# data_right.net
KiCad netlist of a schematic drawn in Altium Designer
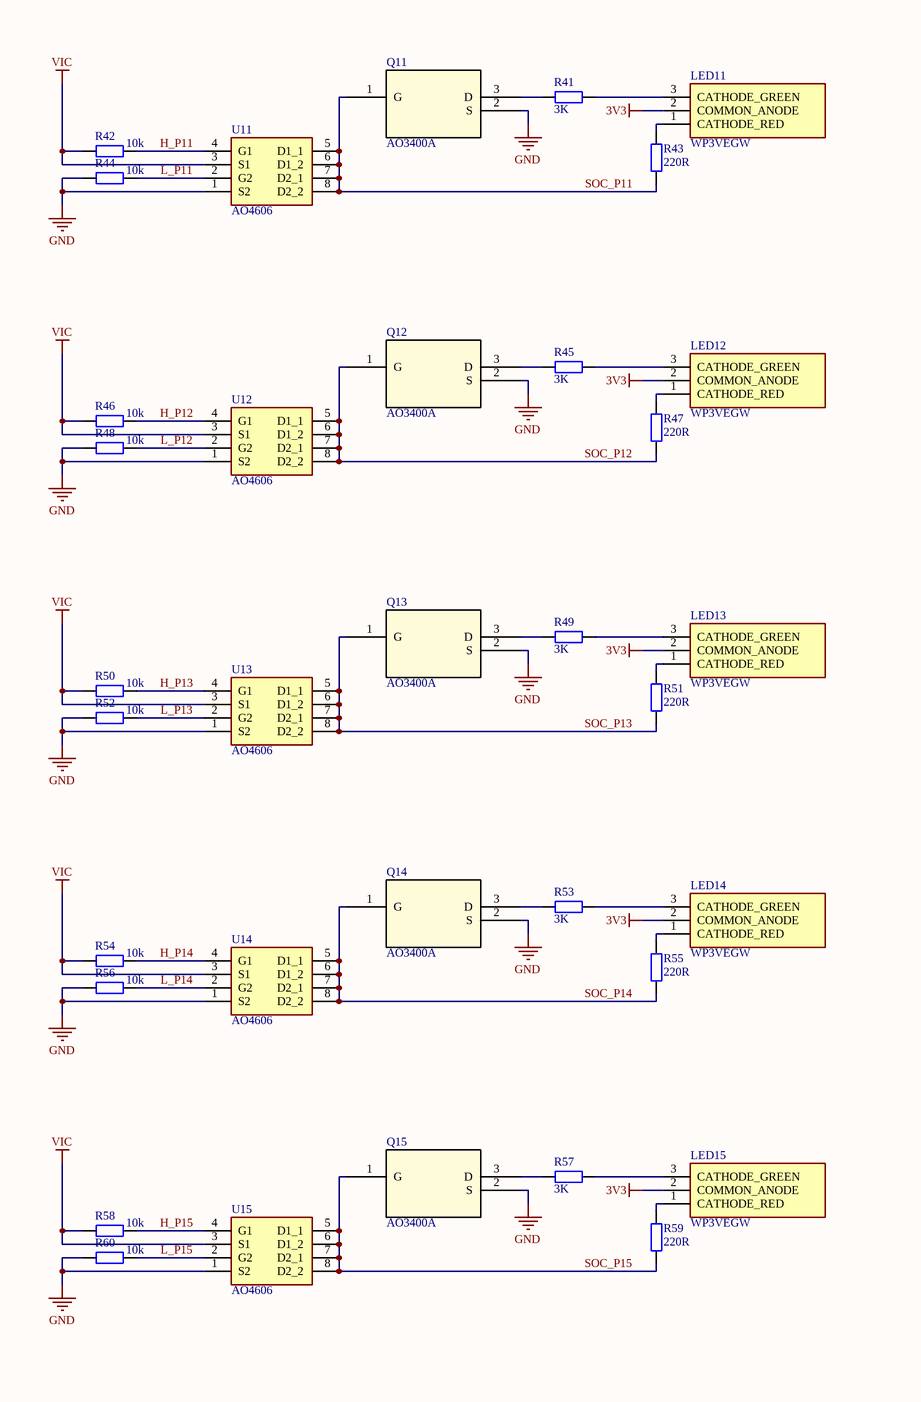
[diagram p0: data_right.SchDoc, top]
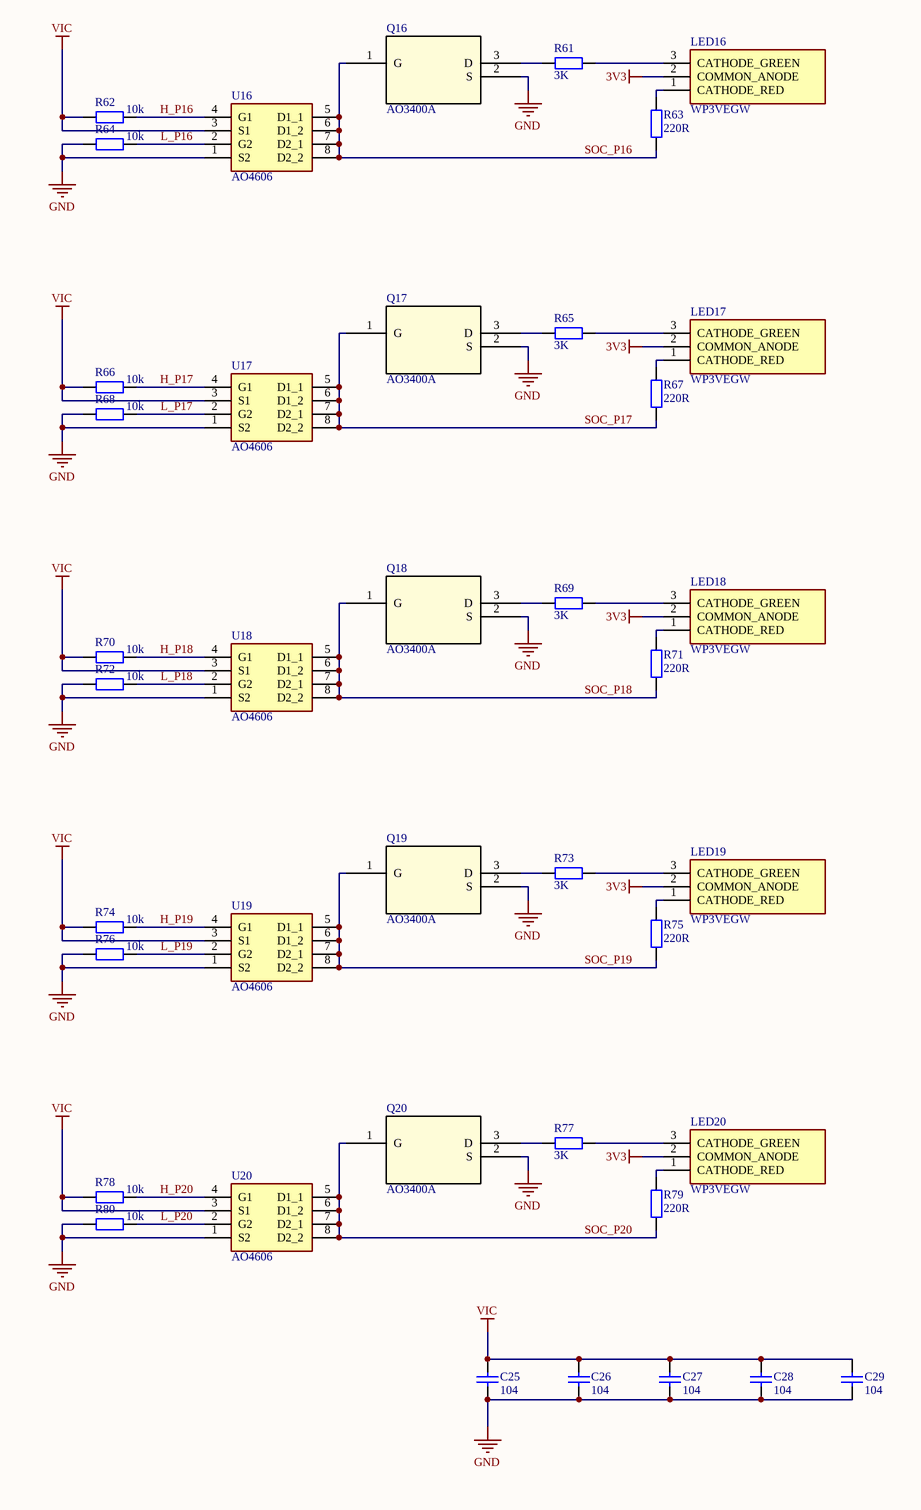
[diagram p1: data_right.SchDoc, bottom]

(export (version "E")
  (design (tool "Eeschema 10.0.6"))
  (components
    (comp (ref "C25")
      (value "104")
      (footprint "tu 0805")
      (description "Dán")
      (libsource (lib "thuvien") (part "Tu 0805 106 16V 10%"))
    )
    (comp (ref "C26")
      (value "104")
      (footprint "tu 0805")
      (description "Dán")
      (libsource (lib "thuvien") (part "Tu 0805 106 16V 10%"))
    )
    (comp (ref "C27")
      (value "104")
      (footprint "tu 0805")
      (description "Dán")
      (libsource (lib "thuvien") (part "Tu 0805 106 16V 10%"))
    )
    (comp (ref "C28")
      (value "104")
      (footprint "tu 0805")
      (description "Dán")
      (libsource (lib "thuvien") (part "Tu 0805 106 16V 10%"))
    )
    (comp (ref "C29")
      (value "104")
      (footprint "tu 0805")
      (description "Dán")
      (libsource (lib "thuvien") (part "Tu 0805 106 16V 10%"))
    )
    (comp (ref "LED11")
      (value "WP3VEGW")
      (footprint "WP3VEGW")
      (description "LED RED/GREEN 3mm")
      (fields (field (name "MOUSER PART NUMBER") "604-WP3VEGW"))
      (libsource (lib "thuvien") (part "WP3VEGW"))
    )
    (comp (ref "LED12")
      (value "WP3VEGW")
      (footprint "WP3VEGW")
      (description "LED RED/GREEN 3mm")
      (fields (field (name "MOUSER PART NUMBER") "604-WP3VEGW"))
      (libsource (lib "thuvien") (part "WP3VEGW"))
    )
    (comp (ref "LED13")
      (value "WP3VEGW")
      (footprint "WP3VEGW")
      (description "LED RED/GREEN 3mm")
      (fields (field (name "MOUSER PART NUMBER") "604-WP3VEGW"))
      (libsource (lib "thuvien") (part "WP3VEGW"))
    )
    (comp (ref "LED14")
      (value "WP3VEGW")
      (footprint "WP3VEGW")
      (description "LED RED/GREEN 3mm")
      (fields (field (name "MOUSER PART NUMBER") "604-WP3VEGW"))
      (libsource (lib "thuvien") (part "WP3VEGW"))
    )
    (comp (ref "LED15")
      (value "WP3VEGW")
      (footprint "WP3VEGW")
      (description "LED RED/GREEN 3mm")
      (fields (field (name "MOUSER PART NUMBER") "604-WP3VEGW"))
      (libsource (lib "thuvien") (part "WP3VEGW"))
    )
    (comp (ref "LED16")
      (value "WP3VEGW")
      (footprint "WP3VEGW")
      (description "LED RED/GREEN 3mm")
      (fields (field (name "MOUSER PART NUMBER") "604-WP3VEGW"))
      (libsource (lib "thuvien") (part "WP3VEGW"))
    )
    (comp (ref "LED17")
      (value "WP3VEGW")
      (footprint "WP3VEGW")
      (description "LED RED/GREEN 3mm")
      (fields (field (name "MOUSER PART NUMBER") "604-WP3VEGW"))
      (libsource (lib "thuvien") (part "WP3VEGW"))
    )
    (comp (ref "LED18")
      (value "WP3VEGW")
      (footprint "WP3VEGW")
      (description "LED RED/GREEN 3mm")
      (fields (field (name "MOUSER PART NUMBER") "604-WP3VEGW"))
      (libsource (lib "thuvien") (part "WP3VEGW"))
    )
    (comp (ref "LED19")
      (value "WP3VEGW")
      (footprint "WP3VEGW")
      (description "LED RED/GREEN 3mm")
      (fields (field (name "MOUSER PART NUMBER") "604-WP3VEGW"))
      (libsource (lib "thuvien") (part "WP3VEGW"))
    )
    (comp (ref "LED20")
      (value "WP3VEGW")
      (footprint "WP3VEGW")
      (description "LED RED/GREEN 3mm")
      (fields (field (name "MOUSER PART NUMBER") "604-WP3VEGW"))
      (libsource (lib "thuvien") (part "WP3VEGW"))
    )
    (comp (ref "Q11")
      (value "AO3400A")
      (footprint "SOT-23-3L_AOS")
      (description "N-MOSFET")
      (fields (field (name "COPYRIGHT") "Copyright (C) 2023 Ultra Librarian. All rights reserved."))
      (libsource (lib "thuvien") (part "AO3400A"))
    )
    (comp (ref "Q12")
      (value "AO3400A")
      (footprint "SOT-23-3L_AOS")
      (description "N-MOSFET")
      (fields (field (name "COPYRIGHT") "Copyright (C) 2023 Ultra Librarian. All rights reserved."))
      (libsource (lib "thuvien") (part "AO3400A"))
    )
    (comp (ref "Q13")
      (value "AO3400A")
      (footprint "SOT-23-3L_AOS")
      (description "N-MOSFET")
      (fields (field (name "COPYRIGHT") "Copyright (C) 2023 Ultra Librarian. All rights reserved."))
      (libsource (lib "thuvien") (part "AO3400A"))
    )
    (comp (ref "Q14")
      (value "AO3400A")
      (footprint "SOT-23-3L_AOS")
      (description "N-MOSFET")
      (fields (field (name "COPYRIGHT") "Copyright (C) 2023 Ultra Librarian. All rights reserved."))
      (libsource (lib "thuvien") (part "AO3400A"))
    )
    (comp (ref "Q15")
      (value "AO3400A")
      (footprint "SOT-23-3L_AOS")
      (description "N-MOSFET")
      (fields (field (name "COPYRIGHT") "Copyright (C) 2023 Ultra Librarian. All rights reserved."))
      (libsource (lib "thuvien") (part "AO3400A"))
    )
    (comp (ref "Q16")
      (value "AO3400A")
      (footprint "SOT-23-3L_AOS")
      (description "N-MOSFET")
      (fields (field (name "COPYRIGHT") "Copyright (C) 2023 Ultra Librarian. All rights reserved."))
      (libsource (lib "thuvien") (part "AO3400A"))
    )
    (comp (ref "Q17")
      (value "AO3400A")
      (footprint "SOT-23-3L_AOS")
      (description "N-MOSFET")
      (fields (field (name "COPYRIGHT") "Copyright (C) 2023 Ultra Librarian. All rights reserved."))
      (libsource (lib "thuvien") (part "AO3400A"))
    )
    (comp (ref "Q18")
      (value "AO3400A")
      (footprint "SOT-23-3L_AOS")
      (description "N-MOSFET")
      (fields (field (name "COPYRIGHT") "Copyright (C) 2023 Ultra Librarian. All rights reserved."))
      (libsource (lib "thuvien") (part "AO3400A"))
    )
    (comp (ref "Q19")
      (value "AO3400A")
      (footprint "SOT-23-3L_AOS")
      (description "N-MOSFET")
      (fields (field (name "COPYRIGHT") "Copyright (C) 2023 Ultra Librarian. All rights reserved."))
      (libsource (lib "thuvien") (part "AO3400A"))
    )
    (comp (ref "Q20")
      (value "AO3400A")
      (footprint "SOT-23-3L_AOS")
      (description "N-MOSFET")
      (fields (field (name "COPYRIGHT") "Copyright (C) 2023 Ultra Librarian. All rights reserved."))
      (libsource (lib "thuvien") (part "AO3400A"))
    )
    (comp (ref "R41")
      (value "3K")
      (footprint "tro smd 0805")
      (description "Dán")
      (libsource (lib "thuvien") (part "Tro 0805 1% 10k"))
    )
    (comp (ref "R42")
      (value "10k")
      (footprint "tro smd 0805")
      (description "Dán")
      (libsource (lib "thuvien") (part "Tro 0805 1% 10k"))
    )
    (comp (ref "R43")
      (value "220R")
      (footprint "tro smd 0805")
      (description "Dán")
      (libsource (lib "thuvien") (part "Tro 0805 1% 10k"))
    )
    (comp (ref "R44")
      (value "10k")
      (footprint "tro smd 0805")
      (description "Dán")
      (libsource (lib "thuvien") (part "Tro 0805 1% 10k"))
    )
    (comp (ref "R45")
      (value "3K")
      (footprint "tro smd 0805")
      (description "Dán")
      (libsource (lib "thuvien") (part "Tro 0805 1% 10k"))
    )
    (comp (ref "R46")
      (value "10k")
      (footprint "tro smd 0805")
      (description "Dán")
      (libsource (lib "thuvien") (part "Tro 0805 1% 10k"))
    )
    (comp (ref "R47")
      (value "220R")
      (footprint "tro smd 0805")
      (description "Dán")
      (libsource (lib "thuvien") (part "Tro 0805 1% 10k"))
    )
    (comp (ref "R48")
      (value "10k")
      (footprint "tro smd 0805")
      (description "Dán")
      (libsource (lib "thuvien") (part "Tro 0805 1% 10k"))
    )
    (comp (ref "R49")
      (value "3K")
      (footprint "tro smd 0805")
      (description "Dán")
      (libsource (lib "thuvien") (part "Tro 0805 1% 10k"))
    )
    (comp (ref "R50")
      (value "10k")
      (footprint "tro smd 0805")
      (description "Dán")
      (libsource (lib "thuvien") (part "Tro 0805 1% 10k"))
    )
    (comp (ref "R51")
      (value "220R")
      (footprint "tro smd 0805")
      (description "Dán")
      (libsource (lib "thuvien") (part "Tro 0805 1% 10k"))
    )
    (comp (ref "R52")
      (value "10k")
      (footprint "tro smd 0805")
      (description "Dán")
      (libsource (lib "thuvien") (part "Tro 0805 1% 10k"))
    )
    (comp (ref "R53")
      (value "3K")
      (footprint "tro smd 0805")
      (description "Dán")
      (libsource (lib "thuvien") (part "Tro 0805 1% 10k"))
    )
    (comp (ref "R54")
      (value "10k")
      (footprint "tro smd 0805")
      (description "Dán")
      (libsource (lib "thuvien") (part "Tro 0805 1% 10k"))
    )
    (comp (ref "R55")
      (value "220R")
      (footprint "tro smd 0805")
      (description "Dán")
      (libsource (lib "thuvien") (part "Tro 0805 1% 10k"))
    )
    (comp (ref "R56")
      (value "10k")
      (footprint "tro smd 0805")
      (description "Dán")
      (libsource (lib "thuvien") (part "Tro 0805 1% 10k"))
    )
    (comp (ref "R57")
      (value "3K")
      (footprint "tro smd 0805")
      (description "Dán")
      (libsource (lib "thuvien") (part "Tro 0805 1% 10k"))
    )
    (comp (ref "R58")
      (value "10k")
      (footprint "tro smd 0805")
      (description "Dán")
      (libsource (lib "thuvien") (part "Tro 0805 1% 10k"))
    )
    (comp (ref "R59")
      (value "220R")
      (footprint "tro smd 0805")
      (description "Dán")
      (libsource (lib "thuvien") (part "Tro 0805 1% 10k"))
    )
    (comp (ref "R60")
      (value "10k")
      (footprint "tro smd 0805")
      (description "Dán")
      (libsource (lib "thuvien") (part "Tro 0805 1% 10k"))
    )
    (comp (ref "R61")
      (value "3K")
      (footprint "tro smd 0805")
      (description "Dán")
      (libsource (lib "thuvien") (part "Tro 0805 1% 10k"))
    )
    (comp (ref "R62")
      (value "10k")
      (footprint "tro smd 0805")
      (description "Dán")
      (libsource (lib "thuvien") (part "Tro 0805 1% 10k"))
    )
    (comp (ref "R63")
      (value "220R")
      (footprint "tro smd 0805")
      (description "Dán")
      (libsource (lib "thuvien") (part "Tro 0805 1% 10k"))
    )
    (comp (ref "R64")
      (value "10k")
      (footprint "tro smd 0805")
      (description "Dán")
      (libsource (lib "thuvien") (part "Tro 0805 1% 10k"))
    )
    (comp (ref "R65")
      (value "3K")
      (footprint "tro smd 0805")
      (description "Dán")
      (libsource (lib "thuvien") (part "Tro 0805 1% 10k"))
    )
    (comp (ref "R66")
      (value "10k")
      (footprint "tro smd 0805")
      (description "Dán")
      (libsource (lib "thuvien") (part "Tro 0805 1% 10k"))
    )
    (comp (ref "R67")
      (value "220R")
      (footprint "tro smd 0805")
      (description "Dán")
      (libsource (lib "thuvien") (part "Tro 0805 1% 10k"))
    )
    (comp (ref "R68")
      (value "10k")
      (footprint "tro smd 0805")
      (description "Dán")
      (libsource (lib "thuvien") (part "Tro 0805 1% 10k"))
    )
    (comp (ref "R69")
      (value "3K")
      (footprint "tro smd 0805")
      (description "Dán")
      (libsource (lib "thuvien") (part "Tro 0805 1% 10k"))
    )
    (comp (ref "R70")
      (value "10k")
      (footprint "tro smd 0805")
      (description "Dán")
      (libsource (lib "thuvien") (part "Tro 0805 1% 10k"))
    )
    (comp (ref "R71")
      (value "220R")
      (footprint "tro smd 0805")
      (description "Dán")
      (libsource (lib "thuvien") (part "Tro 0805 1% 10k"))
    )
    (comp (ref "R72")
      (value "10k")
      (footprint "tro smd 0805")
      (description "Dán")
      (libsource (lib "thuvien") (part "Tro 0805 1% 10k"))
    )
    (comp (ref "R73")
      (value "3K")
      (footprint "tro smd 0805")
      (description "Dán")
      (libsource (lib "thuvien") (part "Tro 0805 1% 10k"))
    )
    (comp (ref "R74")
      (value "10k")
      (footprint "tro smd 0805")
      (description "Dán")
      (libsource (lib "thuvien") (part "Tro 0805 1% 10k"))
    )
    (comp (ref "R75")
      (value "220R")
      (footprint "tro smd 0805")
      (description "Dán")
      (libsource (lib "thuvien") (part "Tro 0805 1% 10k"))
    )
    (comp (ref "R76")
      (value "10k")
      (footprint "tro smd 0805")
      (description "Dán")
      (libsource (lib "thuvien") (part "Tro 0805 1% 10k"))
    )
    (comp (ref "R77")
      (value "3K")
      (footprint "tro smd 0805")
      (description "Dán")
      (libsource (lib "thuvien") (part "Tro 0805 1% 10k"))
    )
    (comp (ref "R78")
      (value "10k")
      (footprint "tro smd 0805")
      (description "Dán")
      (libsource (lib "thuvien") (part "Tro 0805 1% 10k"))
    )
    (comp (ref "R79")
      (value "220R")
      (footprint "tro smd 0805")
      (description "Dán")
      (libsource (lib "thuvien") (part "Tro 0805 1% 10k"))
    )
    (comp (ref "R80")
      (value "10k")
      (footprint "tro smd 0805")
      (description "Dán")
      (libsource (lib "thuvien") (part "Tro 0805 1% 10k"))
    )
    (comp (ref "U11")
      (value "AO4606")
      (footprint "SOIC127P600X175-8N")
      (libsource (lib "thuvien") (part "AO4606"))
    )
    (comp (ref "U12")
      (value "AO4606")
      (footprint "SOIC127P600X175-8N")
      (libsource (lib "thuvien") (part "AO4606"))
    )
    (comp (ref "U13")
      (value "AO4606")
      (footprint "SOIC127P600X175-8N")
      (libsource (lib "thuvien") (part "AO4606"))
    )
    (comp (ref "U14")
      (value "AO4606")
      (footprint "SOIC127P600X175-8N")
      (libsource (lib "thuvien") (part "AO4606"))
    )
    (comp (ref "U15")
      (value "AO4606")
      (footprint "SOIC127P600X175-8N")
      (libsource (lib "thuvien") (part "AO4606"))
    )
    (comp (ref "U16")
      (value "AO4606")
      (footprint "SOIC127P600X175-8N")
      (libsource (lib "thuvien") (part "AO4606"))
    )
    (comp (ref "U17")
      (value "AO4606")
      (footprint "SOIC127P600X175-8N")
      (libsource (lib "thuvien") (part "AO4606"))
    )
    (comp (ref "U18")
      (value "AO4606")
      (footprint "SOIC127P600X175-8N")
      (libsource (lib "thuvien") (part "AO4606"))
    )
    (comp (ref "U19")
      (value "AO4606")
      (footprint "SOIC127P600X175-8N")
      (libsource (lib "thuvien") (part "AO4606"))
    )
    (comp (ref "U20")
      (value "AO4606")
      (footprint "SOIC127P600X175-8N")
      (libsource (lib "thuvien") (part "AO4606"))
    )
  )
  (nets
    (net (code "1") (name "/H_P11") (class "Default")
      (node (ref "R42") (pin "2") (pinfunction "2_2") (pintype "passive"))
      (node (ref "U11") (pin "4") (pinfunction "G1_4") (pintype "passive"))
    )
    (net (code "2") (name "/H_P12") (class "Default")
      (node (ref "R46") (pin "2") (pinfunction "2_2") (pintype "passive"))
      (node (ref "U12") (pin "4") (pinfunction "G1_4") (pintype "passive"))
    )
    (net (code "3") (name "/H_P13") (class "Default")
      (node (ref "R50") (pin "2") (pinfunction "2_2") (pintype "passive"))
      (node (ref "U13") (pin "4") (pinfunction "G1_4") (pintype "passive"))
    )
    (net (code "4") (name "/H_P14") (class "Default")
      (node (ref "R54") (pin "2") (pinfunction "2_2") (pintype "passive"))
      (node (ref "U14") (pin "4") (pinfunction "G1_4") (pintype "passive"))
    )
    (net (code "5") (name "/H_P15") (class "Default")
      (node (ref "R58") (pin "2") (pinfunction "2_2") (pintype "passive"))
      (node (ref "U15") (pin "4") (pinfunction "G1_4") (pintype "passive"))
    )
    (net (code "6") (name "/H_P16") (class "Default")
      (node (ref "R62") (pin "2") (pinfunction "2_2") (pintype "passive"))
      (node (ref "U16") (pin "4") (pinfunction "G1_4") (pintype "passive"))
    )
    (net (code "7") (name "/H_P17") (class "Default")
      (node (ref "R66") (pin "2") (pinfunction "2_2") (pintype "passive"))
      (node (ref "U17") (pin "4") (pinfunction "G1_4") (pintype "passive"))
    )
    (net (code "8") (name "/H_P18") (class "Default")
      (node (ref "R70") (pin "2") (pinfunction "2_2") (pintype "passive"))
      (node (ref "U18") (pin "4") (pinfunction "G1_4") (pintype "passive"))
    )
    (net (code "9") (name "/H_P19") (class "Default")
      (node (ref "R74") (pin "2") (pinfunction "2_2") (pintype "passive"))
      (node (ref "U19") (pin "4") (pinfunction "G1_4") (pintype "passive"))
    )
    (net (code "10") (name "/H_P20") (class "Default")
      (node (ref "R78") (pin "2") (pinfunction "2_2") (pintype "passive"))
      (node (ref "U20") (pin "4") (pinfunction "G1_4") (pintype "passive"))
    )
    (net (code "11") (name "/L_P11") (class "Default")
      (node (ref "R44") (pin "2") (pinfunction "2_2") (pintype "passive"))
      (node (ref "U11") (pin "2") (pinfunction "G2_2") (pintype "passive"))
    )
    (net (code "12") (name "/L_P12") (class "Default")
      (node (ref "R48") (pin "2") (pinfunction "2_2") (pintype "passive"))
      (node (ref "U12") (pin "2") (pinfunction "G2_2") (pintype "passive"))
    )
    (net (code "13") (name "/L_P13") (class "Default")
      (node (ref "R52") (pin "2") (pinfunction "2_2") (pintype "passive"))
      (node (ref "U13") (pin "2") (pinfunction "G2_2") (pintype "passive"))
    )
    (net (code "14") (name "/L_P14") (class "Default")
      (node (ref "R56") (pin "2") (pinfunction "2_2") (pintype "passive"))
      (node (ref "U14") (pin "2") (pinfunction "G2_2") (pintype "passive"))
    )
    (net (code "15") (name "/L_P15") (class "Default")
      (node (ref "R60") (pin "2") (pinfunction "2_2") (pintype "passive"))
      (node (ref "U15") (pin "2") (pinfunction "G2_2") (pintype "passive"))
    )
    (net (code "16") (name "/L_P16") (class "Default")
      (node (ref "R64") (pin "2") (pinfunction "2_2") (pintype "passive"))
      (node (ref "U16") (pin "2") (pinfunction "G2_2") (pintype "passive"))
    )
    (net (code "17") (name "/L_P17") (class "Default")
      (node (ref "R68") (pin "2") (pinfunction "2_2") (pintype "passive"))
      (node (ref "U17") (pin "2") (pinfunction "G2_2") (pintype "passive"))
    )
    (net (code "18") (name "/L_P18") (class "Default")
      (node (ref "R72") (pin "2") (pinfunction "2_2") (pintype "passive"))
      (node (ref "U18") (pin "2") (pinfunction "G2_2") (pintype "passive"))
    )
    (net (code "19") (name "/L_P19") (class "Default")
      (node (ref "R76") (pin "2") (pinfunction "2_2") (pintype "passive"))
      (node (ref "U19") (pin "2") (pinfunction "G2_2") (pintype "passive"))
    )
    (net (code "20") (name "/L_P20") (class "Default")
      (node (ref "R80") (pin "2") (pinfunction "2_2") (pintype "passive"))
      (node (ref "U20") (pin "2") (pinfunction "G2_2") (pintype "passive"))
    )
    (net (code "21") (name "/SOC_P11") (class "Default")
      (node (ref "Q11") (pin "1") (pinfunction "G_1") (pintype "passive"))
      (node (ref "R43") (pin "1") (pinfunction "1_1") (pintype "passive"))
      (node (ref "U11") (pin "5") (pinfunction "D1_1_5") (pintype "passive"))
      (node (ref "U11") (pin "6") (pinfunction "D1_2_6") (pintype "passive"))
      (node (ref "U11") (pin "7") (pinfunction "D2_1_7") (pintype "passive"))
      (node (ref "U11") (pin "8") (pinfunction "D2_2_8") (pintype "passive"))
    )
    (net (code "22") (name "/SOC_P12") (class "Default")
      (node (ref "Q12") (pin "1") (pinfunction "G_1") (pintype "passive"))
      (node (ref "R47") (pin "1") (pinfunction "1_1") (pintype "passive"))
      (node (ref "U12") (pin "5") (pinfunction "D1_1_5") (pintype "passive"))
      (node (ref "U12") (pin "6") (pinfunction "D1_2_6") (pintype "passive"))
      (node (ref "U12") (pin "7") (pinfunction "D2_1_7") (pintype "passive"))
      (node (ref "U12") (pin "8") (pinfunction "D2_2_8") (pintype "passive"))
    )
    (net (code "23") (name "/SOC_P13") (class "Default")
      (node (ref "Q13") (pin "1") (pinfunction "G_1") (pintype "passive"))
      (node (ref "R51") (pin "1") (pinfunction "1_1") (pintype "passive"))
      (node (ref "U13") (pin "5") (pinfunction "D1_1_5") (pintype "passive"))
      (node (ref "U13") (pin "6") (pinfunction "D1_2_6") (pintype "passive"))
      (node (ref "U13") (pin "7") (pinfunction "D2_1_7") (pintype "passive"))
      (node (ref "U13") (pin "8") (pinfunction "D2_2_8") (pintype "passive"))
    )
    (net (code "24") (name "/SOC_P14") (class "Default")
      (node (ref "Q14") (pin "1") (pinfunction "G_1") (pintype "passive"))
      (node (ref "R55") (pin "1") (pinfunction "1_1") (pintype "passive"))
      (node (ref "U14") (pin "5") (pinfunction "D1_1_5") (pintype "passive"))
      (node (ref "U14") (pin "6") (pinfunction "D1_2_6") (pintype "passive"))
      (node (ref "U14") (pin "7") (pinfunction "D2_1_7") (pintype "passive"))
      (node (ref "U14") (pin "8") (pinfunction "D2_2_8") (pintype "passive"))
    )
    (net (code "25") (name "/SOC_P15") (class "Default")
      (node (ref "Q15") (pin "1") (pinfunction "G_1") (pintype "passive"))
      (node (ref "R59") (pin "1") (pinfunction "1_1") (pintype "passive"))
      (node (ref "U15") (pin "5") (pinfunction "D1_1_5") (pintype "passive"))
      (node (ref "U15") (pin "6") (pinfunction "D1_2_6") (pintype "passive"))
      (node (ref "U15") (pin "7") (pinfunction "D2_1_7") (pintype "passive"))
      (node (ref "U15") (pin "8") (pinfunction "D2_2_8") (pintype "passive"))
    )
    (net (code "26") (name "/SOC_P16") (class "Default")
      (node (ref "Q16") (pin "1") (pinfunction "G_1") (pintype "passive"))
      (node (ref "R63") (pin "1") (pinfunction "1_1") (pintype "passive"))
      (node (ref "U16") (pin "5") (pinfunction "D1_1_5") (pintype "passive"))
      (node (ref "U16") (pin "6") (pinfunction "D1_2_6") (pintype "passive"))
      (node (ref "U16") (pin "7") (pinfunction "D2_1_7") (pintype "passive"))
      (node (ref "U16") (pin "8") (pinfunction "D2_2_8") (pintype "passive"))
    )
    (net (code "27") (name "/SOC_P17") (class "Default")
      (node (ref "Q17") (pin "1") (pinfunction "G_1") (pintype "passive"))
      (node (ref "R67") (pin "1") (pinfunction "1_1") (pintype "passive"))
      (node (ref "U17") (pin "5") (pinfunction "D1_1_5") (pintype "passive"))
      (node (ref "U17") (pin "6") (pinfunction "D1_2_6") (pintype "passive"))
      (node (ref "U17") (pin "7") (pinfunction "D2_1_7") (pintype "passive"))
      (node (ref "U17") (pin "8") (pinfunction "D2_2_8") (pintype "passive"))
    )
    (net (code "28") (name "/SOC_P18") (class "Default")
      (node (ref "Q18") (pin "1") (pinfunction "G_1") (pintype "passive"))
      (node (ref "R71") (pin "1") (pinfunction "1_1") (pintype "passive"))
      (node (ref "U18") (pin "5") (pinfunction "D1_1_5") (pintype "passive"))
      (node (ref "U18") (pin "6") (pinfunction "D1_2_6") (pintype "passive"))
      (node (ref "U18") (pin "7") (pinfunction "D2_1_7") (pintype "passive"))
      (node (ref "U18") (pin "8") (pinfunction "D2_2_8") (pintype "passive"))
    )
    (net (code "29") (name "/SOC_P19") (class "Default")
      (node (ref "Q19") (pin "1") (pinfunction "G_1") (pintype "passive"))
      (node (ref "R75") (pin "1") (pinfunction "1_1") (pintype "passive"))
      (node (ref "U19") (pin "5") (pinfunction "D1_1_5") (pintype "passive"))
      (node (ref "U19") (pin "6") (pinfunction "D1_2_6") (pintype "passive"))
      (node (ref "U19") (pin "7") (pinfunction "D2_1_7") (pintype "passive"))
      (node (ref "U19") (pin "8") (pinfunction "D2_2_8") (pintype "passive"))
    )
    (net (code "30") (name "/SOC_P20") (class "Default")
      (node (ref "Q20") (pin "1") (pinfunction "G_1") (pintype "passive"))
      (node (ref "R79") (pin "1") (pinfunction "1_1") (pintype "passive"))
      (node (ref "U20") (pin "5") (pinfunction "D1_1_5") (pintype "passive"))
      (node (ref "U20") (pin "6") (pinfunction "D1_2_6") (pintype "passive"))
      (node (ref "U20") (pin "7") (pinfunction "D2_1_7") (pintype "passive"))
      (node (ref "U20") (pin "8") (pinfunction "D2_2_8") (pintype "passive"))
    )
    (net (code "31") (name "3V3") (class "Default")
      (node (ref "LED11") (pin "2") (pinfunction "COMMON_ANODE_2") (pintype "passive"))
      (node (ref "LED12") (pin "2") (pinfunction "COMMON_ANODE_2") (pintype "passive"))
      (node (ref "LED13") (pin "2") (pinfunction "COMMON_ANODE_2") (pintype "passive"))
      (node (ref "LED14") (pin "2") (pinfunction "COMMON_ANODE_2") (pintype "passive"))
      (node (ref "LED15") (pin "2") (pinfunction "COMMON_ANODE_2") (pintype "passive"))
      (node (ref "LED16") (pin "2") (pinfunction "COMMON_ANODE_2") (pintype "passive"))
      (node (ref "LED17") (pin "2") (pinfunction "COMMON_ANODE_2") (pintype "passive"))
      (node (ref "LED18") (pin "2") (pinfunction "COMMON_ANODE_2") (pintype "passive"))
      (node (ref "LED19") (pin "2") (pinfunction "COMMON_ANODE_2") (pintype "passive"))
      (node (ref "LED20") (pin "2") (pinfunction "COMMON_ANODE_2") (pintype "passive"))
    )
    (net (code "32") (name "GND") (class "Default")
      (node (ref "C25") (pin "2") (pinfunction "2_2") (pintype "passive"))
      (node (ref "C26") (pin "2") (pinfunction "2_2") (pintype "passive"))
      (node (ref "C27") (pin "2") (pinfunction "2_2") (pintype "passive"))
      (node (ref "C28") (pin "2") (pinfunction "2_2") (pintype "passive"))
      (node (ref "C29") (pin "2") (pinfunction "2_2") (pintype "passive"))
      (node (ref "Q11") (pin "2") (pinfunction "S_2") (pintype "passive"))
      (node (ref "Q12") (pin "2") (pinfunction "S_2") (pintype "passive"))
      (node (ref "Q13") (pin "2") (pinfunction "S_2") (pintype "passive"))
      (node (ref "Q14") (pin "2") (pinfunction "S_2") (pintype "passive"))
      (node (ref "Q15") (pin "2") (pinfunction "S_2") (pintype "passive"))
      (node (ref "Q16") (pin "2") (pinfunction "S_2") (pintype "passive"))
      (node (ref "Q17") (pin "2") (pinfunction "S_2") (pintype "passive"))
      (node (ref "Q18") (pin "2") (pinfunction "S_2") (pintype "passive"))
      (node (ref "Q19") (pin "2") (pinfunction "S_2") (pintype "passive"))
      (node (ref "Q20") (pin "2") (pinfunction "S_2") (pintype "passive"))
      (node (ref "R44") (pin "1") (pinfunction "1_1") (pintype "passive"))
      (node (ref "R48") (pin "1") (pinfunction "1_1") (pintype "passive"))
      (node (ref "R52") (pin "1") (pinfunction "1_1") (pintype "passive"))
      (node (ref "R56") (pin "1") (pinfunction "1_1") (pintype "passive"))
      (node (ref "R60") (pin "1") (pinfunction "1_1") (pintype "passive"))
      (node (ref "R64") (pin "1") (pinfunction "1_1") (pintype "passive"))
      (node (ref "R68") (pin "1") (pinfunction "1_1") (pintype "passive"))
      (node (ref "R72") (pin "1") (pinfunction "1_1") (pintype "passive"))
      (node (ref "R76") (pin "1") (pinfunction "1_1") (pintype "passive"))
      (node (ref "R80") (pin "1") (pinfunction "1_1") (pintype "passive"))
      (node (ref "U11") (pin "1") (pinfunction "S2_1") (pintype "passive"))
      (node (ref "U12") (pin "1") (pinfunction "S2_1") (pintype "passive"))
      (node (ref "U13") (pin "1") (pinfunction "S2_1") (pintype "passive"))
      (node (ref "U14") (pin "1") (pinfunction "S2_1") (pintype "passive"))
      (node (ref "U15") (pin "1") (pinfunction "S2_1") (pintype "passive"))
      (node (ref "U16") (pin "1") (pinfunction "S2_1") (pintype "passive"))
      (node (ref "U17") (pin "1") (pinfunction "S2_1") (pintype "passive"))
      (node (ref "U18") (pin "1") (pinfunction "S2_1") (pintype "passive"))
      (node (ref "U19") (pin "1") (pinfunction "S2_1") (pintype "passive"))
      (node (ref "U20") (pin "1") (pinfunction "S2_1") (pintype "passive"))
    )
    (net (code "33") (name "Net-(LED11-CATHODE_GREEN)") (class "Default")
      (node (ref "LED11") (pin "3") (pinfunction "CATHODE_GREEN_3") (pintype "passive"))
      (node (ref "R41") (pin "1") (pinfunction "1_1") (pintype "passive"))
    )
    (net (code "34") (name "Net-(LED11-CATHODE_RED)") (class "Default")
      (node (ref "LED11") (pin "1") (pinfunction "CATHODE_RED_1") (pintype "passive"))
      (node (ref "R43") (pin "2") (pinfunction "2_2") (pintype "passive"))
    )
    (net (code "35") (name "Net-(LED12-CATHODE_GREEN)") (class "Default")
      (node (ref "LED12") (pin "3") (pinfunction "CATHODE_GREEN_3") (pintype "passive"))
      (node (ref "R45") (pin "1") (pinfunction "1_1") (pintype "passive"))
    )
    (net (code "36") (name "Net-(LED12-CATHODE_RED)") (class "Default")
      (node (ref "LED12") (pin "1") (pinfunction "CATHODE_RED_1") (pintype "passive"))
      (node (ref "R47") (pin "2") (pinfunction "2_2") (pintype "passive"))
    )
    (net (code "37") (name "Net-(LED13-CATHODE_GREEN)") (class "Default")
      (node (ref "LED13") (pin "3") (pinfunction "CATHODE_GREEN_3") (pintype "passive"))
      (node (ref "R49") (pin "1") (pinfunction "1_1") (pintype "passive"))
    )
    (net (code "38") (name "Net-(LED13-CATHODE_RED)") (class "Default")
      (node (ref "LED13") (pin "1") (pinfunction "CATHODE_RED_1") (pintype "passive"))
      (node (ref "R51") (pin "2") (pinfunction "2_2") (pintype "passive"))
    )
    (net (code "39") (name "Net-(LED14-CATHODE_GREEN)") (class "Default")
      (node (ref "LED14") (pin "3") (pinfunction "CATHODE_GREEN_3") (pintype "passive"))
      (node (ref "R53") (pin "1") (pinfunction "1_1") (pintype "passive"))
    )
    (net (code "40") (name "Net-(LED14-CATHODE_RED)") (class "Default")
      (node (ref "LED14") (pin "1") (pinfunction "CATHODE_RED_1") (pintype "passive"))
      (node (ref "R55") (pin "2") (pinfunction "2_2") (pintype "passive"))
    )
    (net (code "41") (name "Net-(LED15-CATHODE_GREEN)") (class "Default")
      (node (ref "LED15") (pin "3") (pinfunction "CATHODE_GREEN_3") (pintype "passive"))
      (node (ref "R57") (pin "1") (pinfunction "1_1") (pintype "passive"))
    )
    (net (code "42") (name "Net-(LED15-CATHODE_RED)") (class "Default")
      (node (ref "LED15") (pin "1") (pinfunction "CATHODE_RED_1") (pintype "passive"))
      (node (ref "R59") (pin "2") (pinfunction "2_2") (pintype "passive"))
    )
    (net (code "43") (name "Net-(LED16-CATHODE_GREEN)") (class "Default")
      (node (ref "LED16") (pin "3") (pinfunction "CATHODE_GREEN_3") (pintype "passive"))
      (node (ref "R61") (pin "1") (pinfunction "1_1") (pintype "passive"))
    )
    (net (code "44") (name "Net-(LED16-CATHODE_RED)") (class "Default")
      (node (ref "LED16") (pin "1") (pinfunction "CATHODE_RED_1") (pintype "passive"))
      (node (ref "R63") (pin "2") (pinfunction "2_2") (pintype "passive"))
    )
    (net (code "45") (name "Net-(LED17-CATHODE_GREEN)") (class "Default")
      (node (ref "LED17") (pin "3") (pinfunction "CATHODE_GREEN_3") (pintype "passive"))
      (node (ref "R65") (pin "1") (pinfunction "1_1") (pintype "passive"))
    )
    (net (code "46") (name "Net-(LED17-CATHODE_RED)") (class "Default")
      (node (ref "LED17") (pin "1") (pinfunction "CATHODE_RED_1") (pintype "passive"))
      (node (ref "R67") (pin "2") (pinfunction "2_2") (pintype "passive"))
    )
    (net (code "47") (name "Net-(LED18-CATHODE_GREEN)") (class "Default")
      (node (ref "LED18") (pin "3") (pinfunction "CATHODE_GREEN_3") (pintype "passive"))
      (node (ref "R69") (pin "1") (pinfunction "1_1") (pintype "passive"))
    )
    (net (code "48") (name "Net-(LED18-CATHODE_RED)") (class "Default")
      (node (ref "LED18") (pin "1") (pinfunction "CATHODE_RED_1") (pintype "passive"))
      (node (ref "R71") (pin "2") (pinfunction "2_2") (pintype "passive"))
    )
    (net (code "49") (name "Net-(LED19-CATHODE_GREEN)") (class "Default")
      (node (ref "LED19") (pin "3") (pinfunction "CATHODE_GREEN_3") (pintype "passive"))
      (node (ref "R73") (pin "1") (pinfunction "1_1") (pintype "passive"))
    )
    (net (code "50") (name "Net-(LED19-CATHODE_RED)") (class "Default")
      (node (ref "LED19") (pin "1") (pinfunction "CATHODE_RED_1") (pintype "passive"))
      (node (ref "R75") (pin "2") (pinfunction "2_2") (pintype "passive"))
    )
    (net (code "51") (name "Net-(LED20-CATHODE_GREEN)") (class "Default")
      (node (ref "LED20") (pin "3") (pinfunction "CATHODE_GREEN_3") (pintype "passive"))
      (node (ref "R77") (pin "1") (pinfunction "1_1") (pintype "passive"))
    )
    (net (code "52") (name "Net-(LED20-CATHODE_RED)") (class "Default")
      (node (ref "LED20") (pin "1") (pinfunction "CATHODE_RED_1") (pintype "passive"))
      (node (ref "R79") (pin "2") (pinfunction "2_2") (pintype "passive"))
    )
    (net (code "53") (name "Net-(Q11-D)") (class "Default")
      (node (ref "Q11") (pin "3") (pinfunction "D_3") (pintype "passive"))
      (node (ref "R41") (pin "2") (pinfunction "2_2") (pintype "passive"))
    )
    (net (code "54") (name "Net-(Q12-D)") (class "Default")
      (node (ref "Q12") (pin "3") (pinfunction "D_3") (pintype "passive"))
      (node (ref "R45") (pin "2") (pinfunction "2_2") (pintype "passive"))
    )
    (net (code "55") (name "Net-(Q13-D)") (class "Default")
      (node (ref "Q13") (pin "3") (pinfunction "D_3") (pintype "passive"))
      (node (ref "R49") (pin "2") (pinfunction "2_2") (pintype "passive"))
    )
    (net (code "56") (name "Net-(Q14-D)") (class "Default")
      (node (ref "Q14") (pin "3") (pinfunction "D_3") (pintype "passive"))
      (node (ref "R53") (pin "2") (pinfunction "2_2") (pintype "passive"))
    )
    (net (code "57") (name "Net-(Q15-D)") (class "Default")
      (node (ref "Q15") (pin "3") (pinfunction "D_3") (pintype "passive"))
      (node (ref "R57") (pin "2") (pinfunction "2_2") (pintype "passive"))
    )
    (net (code "58") (name "Net-(Q16-D)") (class "Default")
      (node (ref "Q16") (pin "3") (pinfunction "D_3") (pintype "passive"))
      (node (ref "R61") (pin "2") (pinfunction "2_2") (pintype "passive"))
    )
    (net (code "59") (name "Net-(Q17-D)") (class "Default")
      (node (ref "Q17") (pin "3") (pinfunction "D_3") (pintype "passive"))
      (node (ref "R65") (pin "2") (pinfunction "2_2") (pintype "passive"))
    )
    (net (code "60") (name "Net-(Q18-D)") (class "Default")
      (node (ref "Q18") (pin "3") (pinfunction "D_3") (pintype "passive"))
      (node (ref "R69") (pin "2") (pinfunction "2_2") (pintype "passive"))
    )
    (net (code "61") (name "Net-(Q19-D)") (class "Default")
      (node (ref "Q19") (pin "3") (pinfunction "D_3") (pintype "passive"))
      (node (ref "R73") (pin "2") (pinfunction "2_2") (pintype "passive"))
    )
    (net (code "62") (name "Net-(Q20-D)") (class "Default")
      (node (ref "Q20") (pin "3") (pinfunction "D_3") (pintype "passive"))
      (node (ref "R77") (pin "2") (pinfunction "2_2") (pintype "passive"))
    )
    (net (code "63") (name "VIC") (class "Default")
      (node (ref "C25") (pin "1") (pinfunction "1_1") (pintype "passive"))
      (node (ref "C26") (pin "1") (pinfunction "1_1") (pintype "passive"))
      (node (ref "C27") (pin "1") (pinfunction "1_1") (pintype "passive"))
      (node (ref "C28") (pin "1") (pinfunction "1_1") (pintype "passive"))
      (node (ref "C29") (pin "1") (pinfunction "1_1") (pintype "passive"))
      (node (ref "R42") (pin "1") (pinfunction "1_1") (pintype "passive"))
      (node (ref "R46") (pin "1") (pinfunction "1_1") (pintype "passive"))
      (node (ref "R50") (pin "1") (pinfunction "1_1") (pintype "passive"))
      (node (ref "R54") (pin "1") (pinfunction "1_1") (pintype "passive"))
      (node (ref "R58") (pin "1") (pinfunction "1_1") (pintype "passive"))
      (node (ref "R62") (pin "1") (pinfunction "1_1") (pintype "passive"))
      (node (ref "R66") (pin "1") (pinfunction "1_1") (pintype "passive"))
      (node (ref "R70") (pin "1") (pinfunction "1_1") (pintype "passive"))
      (node (ref "R74") (pin "1") (pinfunction "1_1") (pintype "passive"))
      (node (ref "R78") (pin "1") (pinfunction "1_1") (pintype "passive"))
      (node (ref "U11") (pin "3") (pinfunction "S1_3") (pintype "passive"))
      (node (ref "U12") (pin "3") (pinfunction "S1_3") (pintype "passive"))
      (node (ref "U13") (pin "3") (pinfunction "S1_3") (pintype "passive"))
      (node (ref "U14") (pin "3") (pinfunction "S1_3") (pintype "passive"))
      (node (ref "U15") (pin "3") (pinfunction "S1_3") (pintype "passive"))
      (node (ref "U16") (pin "3") (pinfunction "S1_3") (pintype "passive"))
      (node (ref "U17") (pin "3") (pinfunction "S1_3") (pintype "passive"))
      (node (ref "U18") (pin "3") (pinfunction "S1_3") (pintype "passive"))
      (node (ref "U19") (pin "3") (pinfunction "S1_3") (pintype "passive"))
      (node (ref "U20") (pin "3") (pinfunction "S1_3") (pintype "passive"))
    )
  )
)
